# Grove_-_I2C_ADC.net
KiCad netlist of a schematic drawn in EAGLE
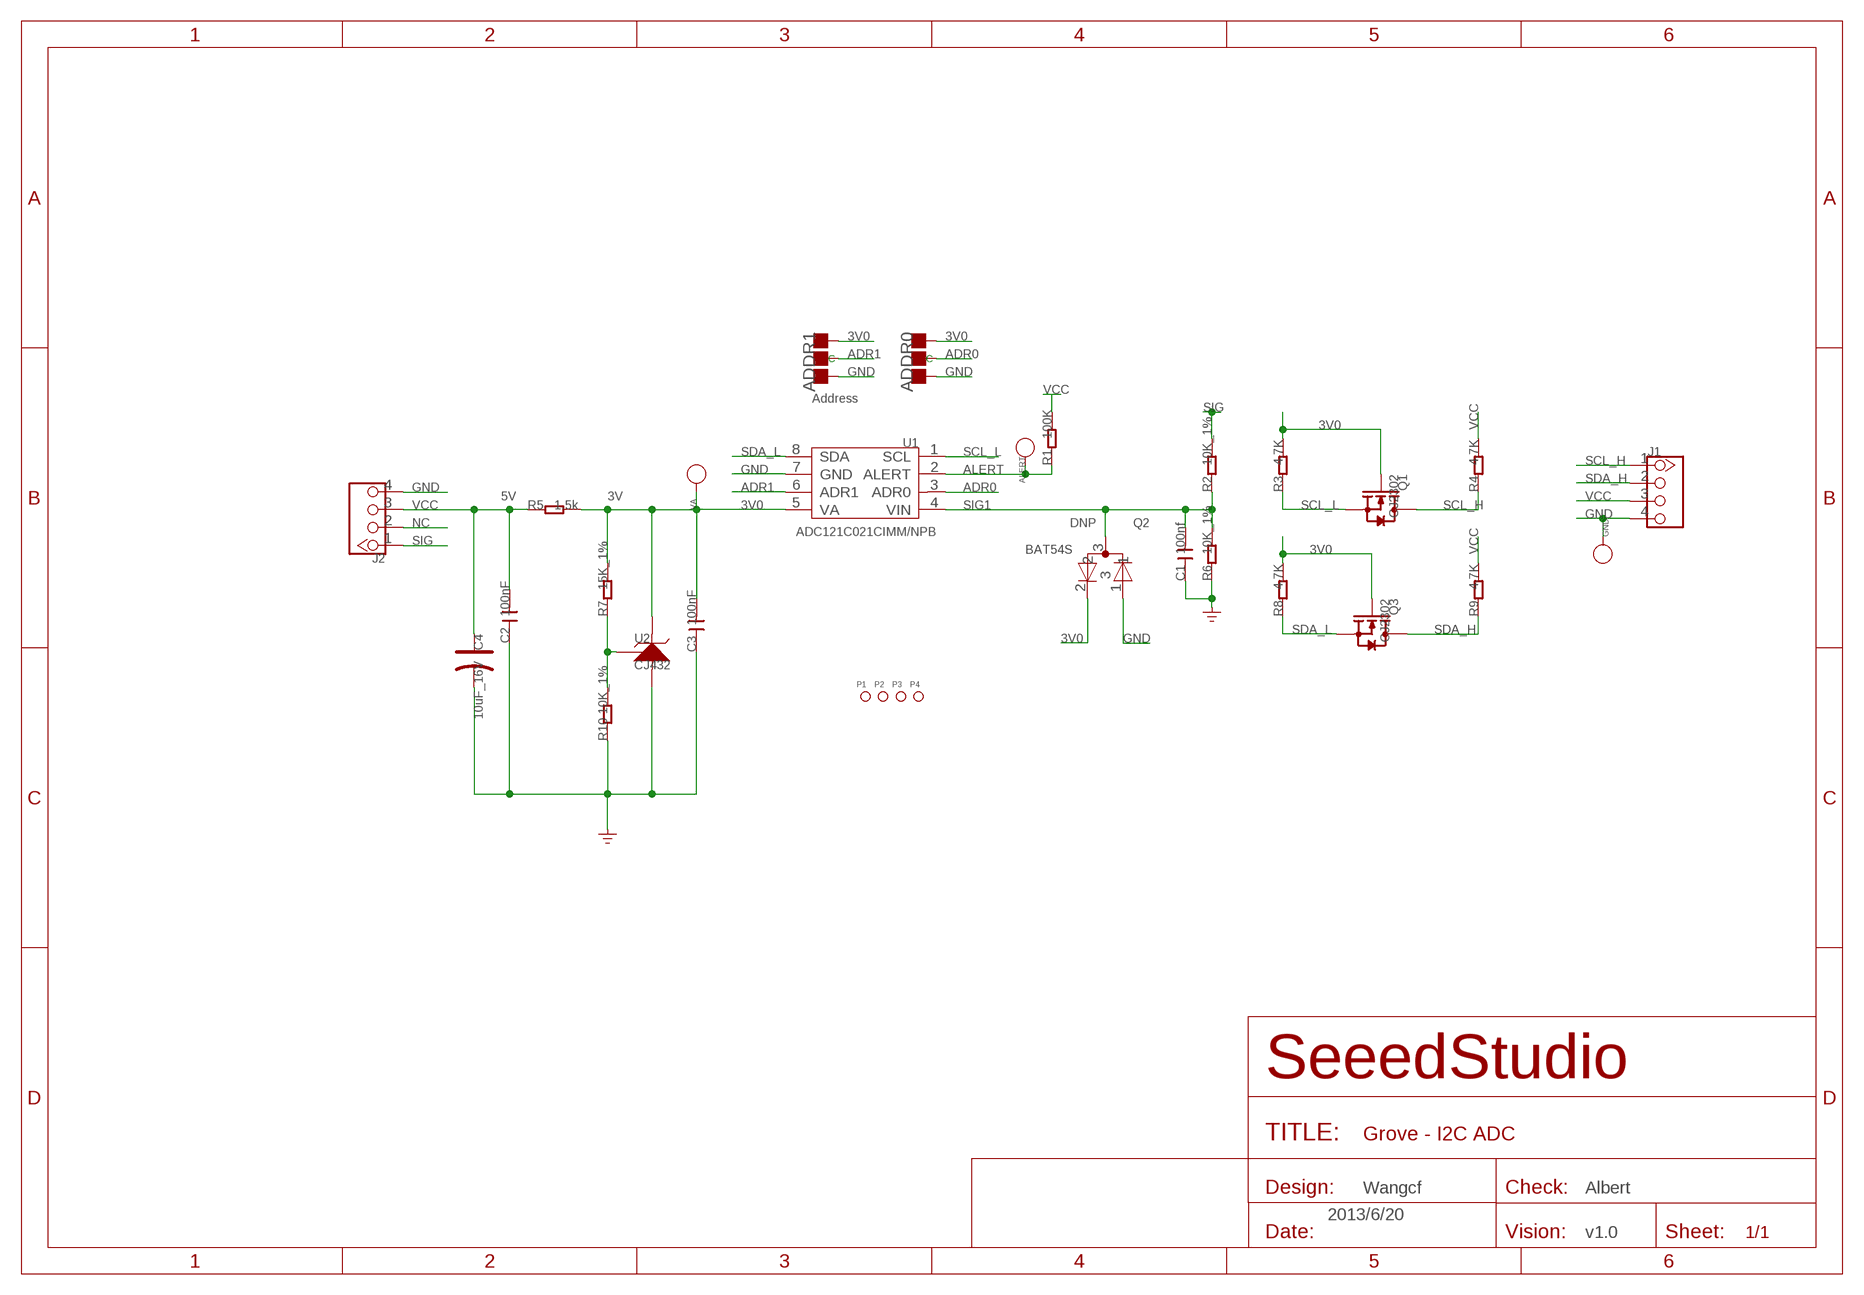
[diagram p0: schematic, sheet 1]

(export (version "E")
  (design (tool "Eeschema 10.0.6"))
  (components
    (comp (ref "ADDR0")
      (value "DNP")
      (footprint "eagle-import:3P-SMD-4.1X1.5")
      (libsource (lib "eagle-import") (part "PAD-JUMPER-3P-4040"))
    )
    (comp (ref "ADDR1")
      (value "DNP")
      (footprint "eagle-import:3P-SMD-4.1X1.5")
      (libsource (lib "eagle-import") (part "PAD-JUMPER-3P-4040"))
    )
    (comp (ref "ALERT")
      (value "DNP")
      (footprint "eagle-import:TP_3535")
      (fields (field (name "PARTNO") "DNP"))
      (libsource (lib "eagle-import") (part "PAD-TEST-POINT-CIRCLE'3535'"))
    )
    (comp (ref "C1")
      (value "100nf")
      (footprint "eagle-import:C0603")
      (libsource (lib "eagle-import") (part "C-0603"))
    )
    (comp (ref "C2")
      (value "100nF")
      (footprint "eagle-import:C0603")
      (libsource (lib "eagle-import") (part "C-0603"))
    )
    (comp (ref "C3")
      (value "100nF")
      (footprint "eagle-import:C0603")
      (libsource (lib "eagle-import") (part "C-0603"))
    )
    (comp (ref "C4")
      (value "10uF_16V")
      (footprint "eagle-import:AVX-A")
      (libsource (lib "eagle-import") (part "CAP-AVX-A"))
    )
    (comp (ref "GND")
      (value "DNP")
      (footprint "eagle-import:TP_3535")
      (libsource (lib "eagle-import") (part "PAD-TEST-POINT-CIRCLE'3535'"))
    )
    (comp (ref "J1")
      (value "TWIG-4P-2.0-2.0")
      (footprint "eagle-import:4P-2.0")
      (libsource (lib "eagle-import") (part "TWIG-4P-2.0-2.0"))
    )
    (comp (ref "J2")
      (value "TWIG-4P-2.0-2.0")
      (footprint "eagle-import:4P-2.0")
      (libsource (lib "eagle-import") (part "TWIG-4P-2.0-2.0"))
    )
    (comp (ref "P1")
      (value "PAD-MARK")
      (footprint "eagle-import:ROUND-MARK-1.0")
      (fields (field (name "PARTNO") "DNP"))
      (libsource (lib "eagle-import") (part "PAD-MARK"))
    )
    (comp (ref "P2")
      (value "PAD-MARK")
      (footprint "eagle-import:ROUND-MARK-1.0")
      (fields (field (name "PARTNO") "DNP"))
      (libsource (lib "eagle-import") (part "PAD-MARK"))
    )
    (comp (ref "P3")
      (value "PAD-MARK")
      (footprint "eagle-import:ROUND-MARK-1.0")
      (fields (field (name "PARTNO") "DNP"))
      (libsource (lib "eagle-import") (part "PAD-MARK"))
    )
    (comp (ref "P4")
      (value "PAD-MARK")
      (footprint "eagle-import:ROUND-MARK-1.0")
      (fields (field (name "PARTNO") "DNP"))
      (libsource (lib "eagle-import") (part "PAD-MARK"))
    )
    (comp (ref "Q1")
      (value "CJ2302")
      (footprint "eagle-import:SOT23")
      (libsource (lib "eagle-import") (part "MOSFET-N'SOT23'"))
    )
    (comp (ref "Q2")
      (value "DNP")
      (footprint "eagle-import:SOT23")
      (libsource (lib "eagle-import") (part "BAV99"))
    )
    (comp (ref "Q3")
      (value "CJ2302")
      (footprint "eagle-import:SOT23")
      (libsource (lib "eagle-import") (part "MOSFET-N'SOT23'"))
    )
    (comp (ref "R1")
      (value "100K")
      (footprint "eagle-import:R0603")
      (libsource (lib "eagle-import") (part "R-0603"))
    )
    (comp (ref "R2")
      (value "10K_1%")
      (footprint "eagle-import:R0603")
      (libsource (lib "eagle-import") (part "R-0603"))
    )
    (comp (ref "R3")
      (value "4.7K")
      (footprint "eagle-import:R0603")
      (libsource (lib "eagle-import") (part "R-0603"))
    )
    (comp (ref "R4")
      (value "4.7K")
      (footprint "eagle-import:R0603")
      (libsource (lib "eagle-import") (part "R-0603"))
    )
    (comp (ref "R5")
      (value "1.5k")
      (footprint "eagle-import:R0603")
      (libsource (lib "eagle-import") (part "R-0603"))
    )
    (comp (ref "R6")
      (value "10K_1%")
      (footprint "eagle-import:R0603")
      (libsource (lib "eagle-import") (part "R-0603"))
    )
    (comp (ref "R7")
      (value "15K_1%")
      (footprint "eagle-import:R0603")
      (libsource (lib "eagle-import") (part "R-0603"))
    )
    (comp (ref "R8")
      (value "4.7K")
      (footprint "eagle-import:R0603")
      (libsource (lib "eagle-import") (part "R-0603"))
    )
    (comp (ref "R9")
      (value "4.7K")
      (footprint "eagle-import:R0603")
      (libsource (lib "eagle-import") (part "R-0603"))
    )
    (comp (ref "R10")
      (value "10K_1%")
      (footprint "eagle-import:R0603")
      (libsource (lib "eagle-import") (part "R-0603"))
    )
    (comp (ref "U1")
      (value "ADC121C021CIMM/NPB")
      (footprint "eagle-import:MSOP8")
      (libsource (lib "eagle-import") (part "ADC121C021'CIMM/NP8'"))
    )
    (comp (ref "U2")
      (value "CJ432")
      (footprint "eagle-import:SOT23")
      (libsource (lib "eagle-import") (part "REFERENCE-SOURCE"))
    )
    (comp (ref "VA")
      (value "DNP")
      (footprint "eagle-import:TP_3535")
      (libsource (lib "eagle-import") (part "PAD-TEST-POINT-CIRCLE'3535'"))
    )
  )
  (nets
    (net (code "1") (name "/3V0") (class "Default")
      (node (ref "ADDR0") (pin "11") (pinfunction "R_11") (pintype "bidirectional"))
      (node (ref "ADDR1") (pin "11") (pinfunction "R_11") (pintype "bidirectional"))
      (node (ref "C3") (pin "2") (pinfunction "2_2") (pintype "passive"))
      (node (ref "Q1") (pin "1") (pinfunction "G_1") (pintype "passive"))
      (node (ref "Q2") (pin "2") (pinfunction "2_2") (pintype "bidirectional"))
      (node (ref "Q3") (pin "1") (pinfunction "G_1") (pintype "passive"))
      (node (ref "R3") (pin "2") (pinfunction "2_2") (pintype "passive"))
      (node (ref "R5") (pin "2") (pinfunction "2_2") (pintype "passive"))
      (node (ref "R7") (pin "2") (pinfunction "2_2") (pintype "passive"))
      (node (ref "R8") (pin "2") (pinfunction "2_2") (pintype "passive"))
      (node (ref "U1") (pin "5") (pinfunction "VA_5") (pintype "bidirectional"))
      (node (ref "U2") (pin "2") (pinfunction "K_2") (pintype "bidirectional"))
      (node (ref "VA") (pin "T") (pinfunction "T_T") (pintype "bidirectional"))
    )
    (net (code "2") (name "/ADR0") (class "Default")
      (node (ref "ADDR0") (pin "MM") (pinfunction "C_MM") (pintype "bidirectional"))
      (node (ref "U1") (pin "3") (pinfunction "ADR0_3") (pintype "bidirectional"))
    )
    (net (code "3") (name "/ADR1") (class "Default")
      (node (ref "ADDR1") (pin "MM") (pinfunction "C_MM") (pintype "bidirectional"))
      (node (ref "U1") (pin "6") (pinfunction "ADR1_6") (pintype "bidirectional"))
    )
    (net (code "4") (name "/ALERT") (class "Default")
      (node (ref "ALERT") (pin "T") (pinfunction "T_T") (pintype "bidirectional"))
      (node (ref "R1") (pin "1") (pinfunction "1_1") (pintype "passive"))
      (node (ref "U1") (pin "2") (pinfunction "ALERT_2") (pintype "bidirectional"))
    )
    (net (code "5") (name "/NC") (class "Default")
      (node (ref "J2") (pin "2") (pinfunction "2_2") (pintype "bidirectional"))
    )
    (net (code "6") (name "/SCL_H") (class "Default")
      (node (ref "J1") (pin "1") (pinfunction "1_1") (pintype "bidirectional"))
      (node (ref "Q1") (pin "3") (pinfunction "D_3") (pintype "passive"))
      (node (ref "R4") (pin "1") (pinfunction "1_1") (pintype "passive"))
    )
    (net (code "7") (name "/SCL_L") (class "Default")
      (node (ref "Q1") (pin "2") (pinfunction "S_2") (pintype "passive"))
      (node (ref "R3") (pin "1") (pinfunction "1_1") (pintype "passive"))
      (node (ref "U1") (pin "1") (pinfunction "SCL_1") (pintype "bidirectional"))
    )
    (net (code "8") (name "/SDA_H") (class "Default")
      (node (ref "J1") (pin "2") (pinfunction "2_2") (pintype "bidirectional"))
      (node (ref "Q3") (pin "3") (pinfunction "D_3") (pintype "passive"))
      (node (ref "R9") (pin "1") (pinfunction "1_1") (pintype "passive"))
    )
    (net (code "9") (name "/SDA_L") (class "Default")
      (node (ref "Q3") (pin "2") (pinfunction "S_2") (pintype "passive"))
      (node (ref "R8") (pin "1") (pinfunction "1_1") (pintype "passive"))
      (node (ref "U1") (pin "8") (pinfunction "SDA_8") (pintype "bidirectional"))
    )
    (net (code "10") (name "/SIG") (class "Default")
      (node (ref "J2") (pin "1") (pinfunction "1_1") (pintype "bidirectional"))
      (node (ref "R2") (pin "2") (pinfunction "2_2") (pintype "passive"))
    )
    (net (code "11") (name "/SIG1") (class "Default")
      (node (ref "C1") (pin "2") (pinfunction "2_2") (pintype "passive"))
      (node (ref "Q2") (pin "3") (pinfunction "3_3") (pintype "bidirectional"))
      (node (ref "R2") (pin "1") (pinfunction "1_1") (pintype "passive"))
      (node (ref "R6") (pin "2") (pinfunction "2_2") (pintype "passive"))
      (node (ref "U1") (pin "4") (pinfunction "VIN_4") (pintype "bidirectional"))
    )
    (net (code "12") (name "/VCC") (class "Default")
      (node (ref "C2") (pin "2") (pinfunction "2_2") (pintype "passive"))
      (node (ref "C4") (pin "+") (pinfunction "+_+") (pintype "passive"))
      (node (ref "J1") (pin "3") (pinfunction "3_3") (pintype "bidirectional"))
      (node (ref "J2") (pin "3") (pinfunction "3_3") (pintype "bidirectional"))
      (node (ref "R4") (pin "2") (pinfunction "2_2") (pintype "passive"))
      (node (ref "R5") (pin "1") (pinfunction "1_1") (pintype "passive"))
      (node (ref "R9") (pin "2") (pinfunction "2_2") (pintype "passive"))
    )
    (net (code "13") (name "GND_POWER") (class "Default")
      (node (ref "ADDR0") (pin "00") (pinfunction "L_00") (pintype "bidirectional"))
      (node (ref "ADDR1") (pin "00") (pinfunction "L_00") (pintype "bidirectional"))
      (node (ref "C1") (pin "1") (pinfunction "1_1") (pintype "passive"))
      (node (ref "C2") (pin "1") (pinfunction "1_1") (pintype "passive"))
      (node (ref "C3") (pin "1") (pinfunction "1_1") (pintype "passive"))
      (node (ref "C4") (pin "-") (pinfunction "-_-") (pintype "passive"))
      (node (ref "GND") (pin "T") (pinfunction "T_T") (pintype "bidirectional"))
      (node (ref "J1") (pin "4") (pinfunction "4_4") (pintype "bidirectional"))
      (node (ref "J2") (pin "4") (pinfunction "4_4") (pintype "bidirectional"))
      (node (ref "Q2") (pin "1") (pinfunction "1_1") (pintype "bidirectional"))
      (node (ref "R10") (pin "1") (pinfunction "1_1") (pintype "passive"))
      (node (ref "R6") (pin "1") (pinfunction "1_1") (pintype "passive"))
      (node (ref "U1") (pin "7") (pinfunction "GND_7") (pintype "bidirectional"))
      (node (ref "U2") (pin "3") (pinfunction "A_3") (pintype "bidirectional"))
    )
    (net (code "14") (name "Net-(U2-R)") (class "Default")
      (node (ref "R10") (pin "2") (pinfunction "2_2") (pintype "passive"))
      (node (ref "R7") (pin "1") (pinfunction "1_1") (pintype "passive"))
      (node (ref "U2") (pin "1") (pinfunction "R_1") (pintype "bidirectional"))
    )
    (net (code "15") (name "unconnected-(R1-Pad2)") (class "Default")
      (node (ref "R1") (pin "2") (pinfunction "2_2") (pintype "passive"))
    )
  )
)
